# as14120_x31_fpga_cypress.net
KiCad netlist of a schematic drawn in Altium Designer
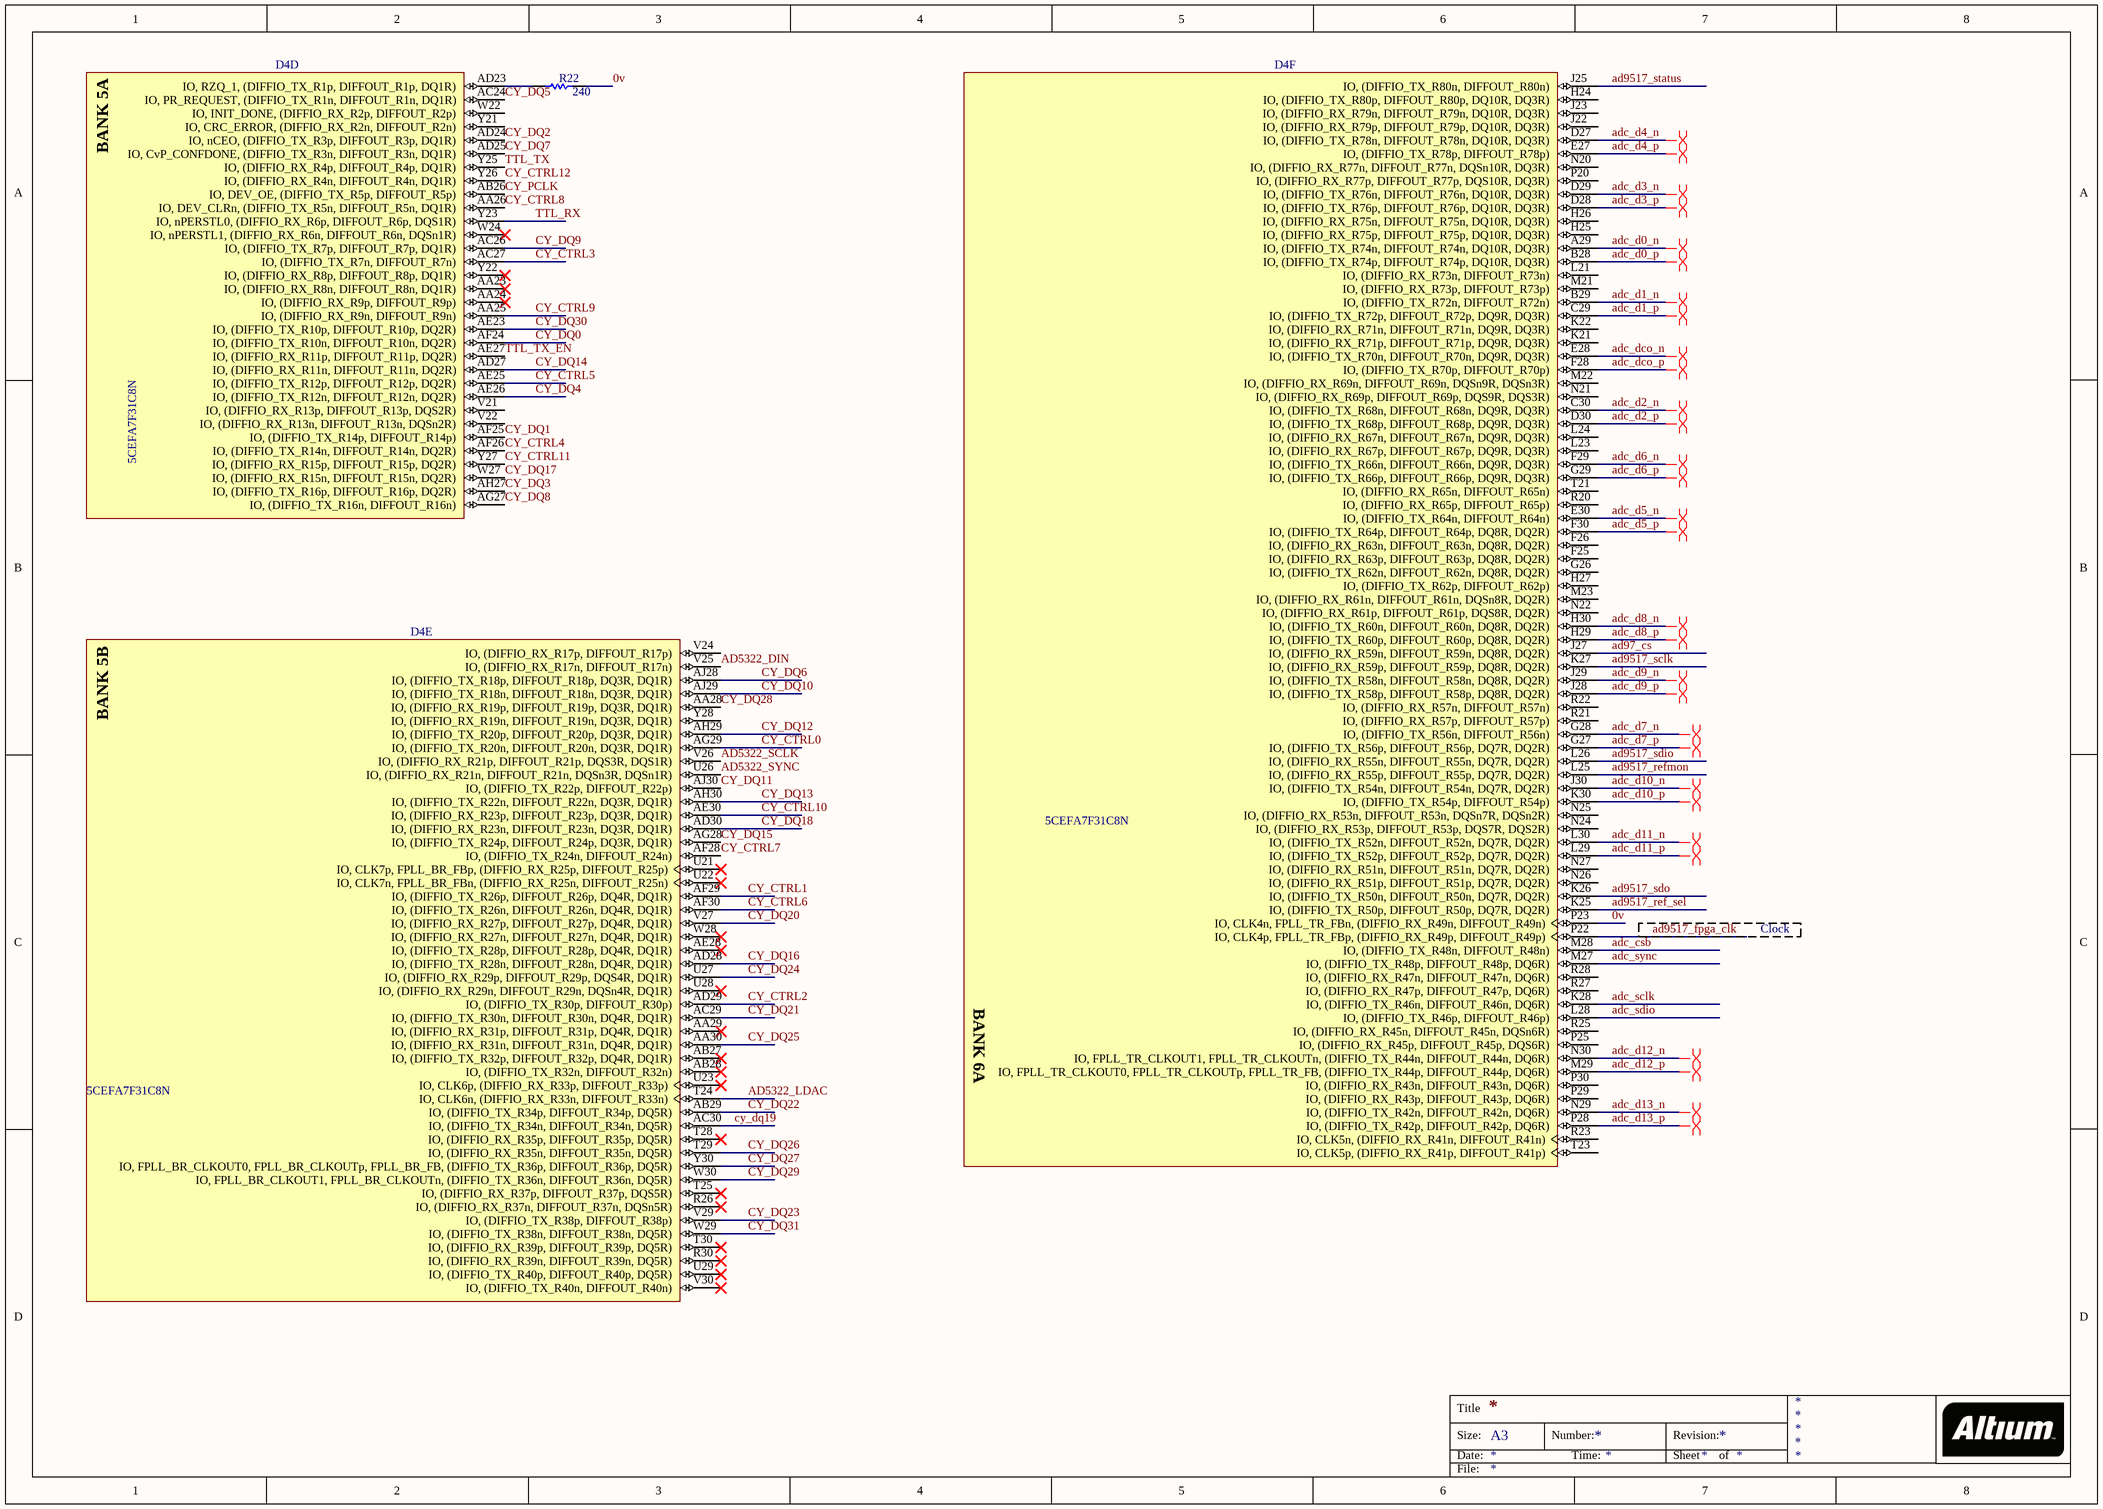
[diagram p0: as14120_x31_fpga_cypress.SchDoc]

(export (version "E")
  (design (tool "Eeschema 10.0.6"))
  (components
    (comp (ref "D4")
      (value "5CEFA7F31C8N")
      (footprint "ALTR-896-FBGA-2000A")
      (fields (field (name "MANUFACTURER") "Altera"))
      (libsource (lib "Altera Cyclone V E") (part "5CEFA7F31C8N"))
    )
    (comp (ref "R22")
      (value "240")
      (footprint "RESC0603(1608)_L")
      (description "1K 0.1W 5% 0603 (1608 Metric)  SMD")
      (fields (field (name "TOLERANCE") "5 %") (field (name "POWER") "0.1 W"))
      (libsource (lib "as14120") (part "RES_0603"))
    )
  )
  (nets
    (net (code "1") (name "/0v") (class "Default")
      (node (ref "D4") (pin "P23") (pinfunction "IO,_CLK4n,_FPLL_TR_FBn,_(DIFFIO_RX_R49n,_DIFFOUT_R49n)_P23") (pintype "bidirectional"))
      (node (ref "R22") (pin "2") (pinfunction "2_2") (pintype "passive"))
    )
    (net (code "2") (name "/AD5322_DIN") (class "Default")
      (node (ref "D4") (pin "V25") (pinfunction "IO,_(DIFFIO_RX_R17n,_DIFFOUT_R17n)_V25") (pintype "bidirectional"))
    )
    (net (code "3") (name "/AD5322_LDAC") (class "Default")
      (node (ref "D4") (pin "T24") (pinfunction "IO,_CLK6n,_(DIFFIO_RX_R33n,_DIFFOUT_R33n)_T24") (pintype "bidirectional"))
    )
    (net (code "4") (name "/AD5322_SCLK") (class "Default")
      (node (ref "D4") (pin "V26") (pinfunction "IO,_(DIFFIO_RX_R21p,_DIFFOUT_R21p,_DQS3R,_DQS1R)_V26") (pintype "bidirectional"))
    )
    (net (code "5") (name "/AD5322_SYNC") (class "Default")
      (node (ref "D4") (pin "U26") (pinfunction "IO,_(DIFFIO_RX_R21n,_DIFFOUT_R21n,_DQSn3R,_DQSn1R)_U26") (pintype "bidirectional"))
    )
    (net (code "6") (name "/CY_CTRL0") (class "Default")
      (node (ref "D4") (pin "AG29") (pinfunction "IO,_(DIFFIO_TX_R20n,_DIFFOUT_R20n,_DQ3R,_DQ1R)_AG29") (pintype "bidirectional"))
    )
    (net (code "7") (name "/CY_CTRL1") (class "Default")
      (node (ref "D4") (pin "AF29") (pinfunction "IO,_(DIFFIO_TX_R26p,_DIFFOUT_R26p,_DQ4R,_DQ1R)_AF29") (pintype "bidirectional"))
    )
    (net (code "8") (name "/CY_CTRL2") (class "Default")
      (node (ref "D4") (pin "AD29") (pinfunction "IO,_(DIFFIO_TX_R30p,_DIFFOUT_R30p)_AD29") (pintype "bidirectional"))
    )
    (net (code "9") (name "/CY_CTRL3") (class "Default")
      (node (ref "D4") (pin "AC27") (pinfunction "IO,_(DIFFIO_TX_R7n,_DIFFOUT_R7n)_AC27") (pintype "bidirectional"))
    )
    (net (code "10") (name "/CY_CTRL4") (class "Default")
      (node (ref "D4") (pin "AF26") (pinfunction "IO,_(DIFFIO_TX_R14n,_DIFFOUT_R14n,_DQ2R)_AF26") (pintype "bidirectional"))
    )
    (net (code "11") (name "/CY_CTRL5") (class "Default")
      (node (ref "D4") (pin "AE25") (pinfunction "IO,_(DIFFIO_TX_R12p,_DIFFOUT_R12p,_DQ2R)_AE25") (pintype "bidirectional"))
    )
    (net (code "12") (name "/CY_CTRL6") (class "Default")
      (node (ref "D4") (pin "AF30") (pinfunction "IO,_(DIFFIO_TX_R26n,_DIFFOUT_R26n,_DQ4R,_DQ1R)_AF30") (pintype "bidirectional"))
    )
    (net (code "13") (name "/CY_CTRL7") (class "Default")
      (node (ref "D4") (pin "AF28") (pinfunction "IO,_(DIFFIO_TX_R24n,_DIFFOUT_R24n)_AF28") (pintype "bidirectional"))
    )
    (net (code "14") (name "/CY_CTRL8") (class "Default")
      (node (ref "D4") (pin "AA26") (pinfunction "IO,_DEV_CLRn,_(DIFFIO_TX_R5n,_DIFFOUT_R5n,_DQ1R)_AA26") (pintype "bidirectional"))
    )
    (net (code "15") (name "/CY_CTRL9") (class "Default")
      (node (ref "D4") (pin "AA25") (pinfunction "IO,_(DIFFIO_RX_R9n,_DIFFOUT_R9n)_AA25") (pintype "bidirectional"))
    )
    (net (code "16") (name "/CY_CTRL10") (class "Default")
      (node (ref "D4") (pin "AE30") (pinfunction "IO,_(DIFFIO_RX_R23p,_DIFFOUT_R23p,_DQ3R,_DQ1R)_AE30") (pintype "bidirectional"))
    )
    (net (code "17") (name "/CY_CTRL11") (class "Default")
      (node (ref "D4") (pin "Y27") (pinfunction "IO,_(DIFFIO_RX_R15p,_DIFFOUT_R15p,_DQ2R)_Y27") (pintype "bidirectional"))
    )
    (net (code "18") (name "/CY_CTRL12") (class "Default")
      (node (ref "D4") (pin "Y26") (pinfunction "IO,_(DIFFIO_RX_R4n,_DIFFOUT_R4n,_DQ1R)_Y26") (pintype "bidirectional"))
    )
    (net (code "19") (name "/CY_DQ0") (class "Default")
      (node (ref "D4") (pin "AF24") (pinfunction "IO,_(DIFFIO_TX_R10n,_DIFFOUT_R10n,_DQ2R)_AF24") (pintype "bidirectional"))
    )
    (net (code "20") (name "/CY_DQ1") (class "Default")
      (node (ref "D4") (pin "AF25") (pinfunction "IO,_(DIFFIO_TX_R14p,_DIFFOUT_R14p)_AF25") (pintype "bidirectional"))
    )
    (net (code "21") (name "/CY_DQ2") (class "Default")
      (node (ref "D4") (pin "AD24") (pinfunction "IO,_nCEO,_(DIFFIO_TX_R3p,_DIFFOUT_R3p,_DQ1R)_AD24") (pintype "bidirectional"))
    )
    (net (code "22") (name "/CY_DQ3") (class "Default")
      (node (ref "D4") (pin "AH27") (pinfunction "IO,_(DIFFIO_TX_R16p,_DIFFOUT_R16p,_DQ2R)_AH27") (pintype "bidirectional"))
    )
    (net (code "23") (name "/CY_DQ4") (class "Default")
      (node (ref "D4") (pin "AE26") (pinfunction "IO,_(DIFFIO_TX_R12n,_DIFFOUT_R12n,_DQ2R)_AE26") (pintype "bidirectional"))
    )
    (net (code "24") (name "/CY_DQ5") (class "Default")
      (node (ref "D4") (pin "AC24") (pinfunction "IO,_PR_REQUEST,_(DIFFIO_TX_R1n,_DIFFOUT_R1n,_DQ1R)_AC24") (pintype "bidirectional"))
    )
    (net (code "25") (name "/CY_DQ6") (class "Default")
      (node (ref "D4") (pin "AJ28") (pinfunction "IO,_(DIFFIO_TX_R18p,_DIFFOUT_R18p,_DQ3R,_DQ1R)_AJ28") (pintype "bidirectional"))
    )
    (net (code "26") (name "/CY_DQ7") (class "Default")
      (node (ref "D4") (pin "AD25") (pinfunction "IO,_CvP_CONFDONE,_(DIFFIO_TX_R3n,_DIFFOUT_R3n,_DQ1R)_AD25") (pintype "bidirectional"))
    )
    (net (code "27") (name "/CY_DQ8") (class "Default")
      (node (ref "D4") (pin "AG27") (pinfunction "IO,_(DIFFIO_TX_R16n,_DIFFOUT_R16n)_AG27") (pintype "bidirectional"))
    )
    (net (code "28") (name "/CY_DQ9") (class "Default")
      (node (ref "D4") (pin "AC26") (pinfunction "IO,_(DIFFIO_TX_R7p,_DIFFOUT_R7p,_DQ1R)_AC26") (pintype "bidirectional"))
    )
    (net (code "29") (name "/CY_DQ10") (class "Default")
      (node (ref "D4") (pin "AJ29") (pinfunction "IO,_(DIFFIO_TX_R18n,_DIFFOUT_R18n,_DQ3R,_DQ1R)_AJ29") (pintype "bidirectional"))
    )
    (net (code "30") (name "/CY_DQ11") (class "Default")
      (node (ref "D4") (pin "AJ30") (pinfunction "IO,_(DIFFIO_TX_R22p,_DIFFOUT_R22p)_AJ30") (pintype "bidirectional"))
    )
    (net (code "31") (name "/CY_DQ12") (class "Default")
      (node (ref "D4") (pin "AH29") (pinfunction "IO,_(DIFFIO_TX_R20p,_DIFFOUT_R20p,_DQ3R,_DQ1R)_AH29") (pintype "bidirectional"))
    )
    (net (code "32") (name "/CY_DQ13") (class "Default")
      (node (ref "D4") (pin "AH30") (pinfunction "IO,_(DIFFIO_TX_R22n,_DIFFOUT_R22n,_DQ3R,_DQ1R)_AH30") (pintype "bidirectional"))
    )
    (net (code "33") (name "/CY_DQ14") (class "Default")
      (node (ref "D4") (pin "AD27") (pinfunction "IO,_(DIFFIO_RX_R11n,_DIFFOUT_R11n,_DQ2R)_AD27") (pintype "bidirectional"))
    )
    (net (code "34") (name "/CY_DQ15") (class "Default")
      (node (ref "D4") (pin "AG28") (pinfunction "IO,_(DIFFIO_TX_R24p,_DIFFOUT_R24p,_DQ3R,_DQ1R)_AG28") (pintype "bidirectional"))
    )
    (net (code "35") (name "/CY_DQ16") (class "Default")
      (node (ref "D4") (pin "AD28") (pinfunction "IO,_(DIFFIO_TX_R28n,_DIFFOUT_R28n,_DQ4R,_DQ1R)_AD28") (pintype "bidirectional"))
    )
    (net (code "36") (name "/CY_DQ17") (class "Default")
      (node (ref "D4") (pin "W27") (pinfunction "IO,_(DIFFIO_RX_R15n,_DIFFOUT_R15n,_DQ2R)_W27") (pintype "bidirectional"))
    )
    (net (code "37") (name "/CY_DQ18") (class "Default")
      (node (ref "D4") (pin "AD30") (pinfunction "IO,_(DIFFIO_RX_R23n,_DIFFOUT_R23n,_DQ3R,_DQ1R)_AD30") (pintype "bidirectional"))
    )
    (net (code "38") (name "/CY_DQ20") (class "Default")
      (node (ref "D4") (pin "V27") (pinfunction "IO,_(DIFFIO_RX_R27p,_DIFFOUT_R27p,_DQ4R,_DQ1R)_V27") (pintype "bidirectional"))
    )
    (net (code "39") (name "/CY_DQ21") (class "Default")
      (node (ref "D4") (pin "AC29") (pinfunction "IO,_(DIFFIO_TX_R30n,_DIFFOUT_R30n,_DQ4R,_DQ1R)_AC29") (pintype "bidirectional"))
    )
    (net (code "40") (name "/CY_DQ22") (class "Default")
      (node (ref "D4") (pin "AB29") (pinfunction "IO,_(DIFFIO_TX_R34p,_DIFFOUT_R34p,_DQ5R)_AB29") (pintype "bidirectional"))
    )
    (net (code "41") (name "/CY_DQ23") (class "Default")
      (node (ref "D4") (pin "V29") (pinfunction "IO,_(DIFFIO_TX_R38p,_DIFFOUT_R38p)_V29") (pintype "bidirectional"))
    )
    (net (code "42") (name "/CY_DQ24") (class "Default")
      (node (ref "D4") (pin "U27") (pinfunction "IO,_(DIFFIO_RX_R29p,_DIFFOUT_R29p,_DQS4R,_DQ1R)_U27") (pintype "bidirectional"))
    )
    (net (code "43") (name "/CY_DQ25") (class "Default")
      (node (ref "D4") (pin "AA30") (pinfunction "IO,_(DIFFIO_RX_R31n,_DIFFOUT_R31n,_DQ4R,_DQ1R)_AA30") (pintype "bidirectional"))
    )
    (net (code "44") (name "/CY_DQ26") (class "Default")
      (node (ref "D4") (pin "T29") (pinfunction "IO,_(DIFFIO_RX_R35n,_DIFFOUT_R35n,_DQ5R)_T29") (pintype "bidirectional"))
    )
    (net (code "45") (name "/CY_DQ27") (class "Default")
      (node (ref "D4") (pin "Y30") (pinfunction "IO,_FPLL_BR_CLKOUT0,_FPLL_BR_CLKOUTp,_FPLL_BR_FB,_(DIFFIO_TX_R36p,_DIFFOUT_R36p,_DQ5R)_Y30") (pintype "bidirectional"))
    )
    (net (code "46") (name "/CY_DQ28") (class "Default")
      (node (ref "D4") (pin "AA28") (pinfunction "IO,_(DIFFIO_RX_R19p,_DIFFOUT_R19p,_DQ3R,_DQ1R)_AA28") (pintype "bidirectional"))
    )
    (net (code "47") (name "/CY_DQ29") (class "Default")
      (node (ref "D4") (pin "W30") (pinfunction "IO,_FPLL_BR_CLKOUT1,_FPLL_BR_CLKOUTn,_(DIFFIO_TX_R36n,_DIFFOUT_R36n,_DQ5R)_W30") (pintype "bidirectional"))
    )
    (net (code "48") (name "/CY_DQ30") (class "Default")
      (node (ref "D4") (pin "AE23") (pinfunction "IO,_(DIFFIO_TX_R10p,_DIFFOUT_R10p,_DQ2R)_AE23") (pintype "bidirectional"))
    )
    (net (code "49") (name "/CY_DQ31") (class "Default")
      (node (ref "D4") (pin "W29") (pinfunction "IO,_(DIFFIO_TX_R38n,_DIFFOUT_R38n,_DQ5R)_W29") (pintype "bidirectional"))
    )
    (net (code "50") (name "/CY_PCLK") (class "Default")
      (node (ref "D4") (pin "AB26") (pinfunction "IO,_DEV_OE,_(DIFFIO_TX_R5p,_DIFFOUT_R5p)_AB26") (pintype "bidirectional"))
    )
    (net (code "51") (name "/TTL_RX") (class "Default")
      (node (ref "D4") (pin "Y23") (pinfunction "IO,_nPERSTL0,_(DIFFIO_RX_R6p,_DIFFOUT_R6p,_DQS1R)_Y23") (pintype "bidirectional"))
    )
    (net (code "52") (name "/TTL_TX") (class "Default")
      (node (ref "D4") (pin "Y25") (pinfunction "IO,_(DIFFIO_RX_R4p,_DIFFOUT_R4p,_DQ1R)_Y25") (pintype "bidirectional"))
    )
    (net (code "53") (name "/TTL_TX_EN") (class "Default")
      (node (ref "D4") (pin "AE27") (pinfunction "IO,_(DIFFIO_RX_R11p,_DIFFOUT_R11p,_DQ2R)_AE27") (pintype "bidirectional"))
    )
    (net (code "54") (name "/ad97_cs") (class "Default")
      (node (ref "D4") (pin "J27") (pinfunction "IO,_(DIFFIO_RX_R59n,_DIFFOUT_R59n,_DQ8R,_DQ2R)_J27") (pintype "bidirectional"))
    )
    (net (code "55") (name "/ad9517_fpga_clk") (class "Default")
      (node (ref "D4") (pin "P22") (pinfunction "IO,_CLK4p,_FPLL_TR_FBp,_(DIFFIO_RX_R49p,_DIFFOUT_R49p)_P22") (pintype "bidirectional"))
    )
    (net (code "56") (name "/ad9517_ref_sel") (class "Default")
      (node (ref "D4") (pin "K25") (pinfunction "IO,_(DIFFIO_TX_R50p,_DIFFOUT_R50p,_DQ7R,_DQ2R)_K25") (pintype "bidirectional"))
    )
    (net (code "57") (name "/ad9517_refmon") (class "Default")
      (node (ref "D4") (pin "L25") (pinfunction "IO,_(DIFFIO_RX_R55p,_DIFFOUT_R55p,_DQ7R,_DQ2R)_L25") (pintype "bidirectional"))
    )
    (net (code "58") (name "/ad9517_sclk") (class "Default")
      (node (ref "D4") (pin "K27") (pinfunction "IO,_(DIFFIO_RX_R59p,_DIFFOUT_R59p,_DQ8R,_DQ2R)_K27") (pintype "bidirectional"))
    )
    (net (code "59") (name "/ad9517_sdio") (class "Default")
      (node (ref "D4") (pin "L26") (pinfunction "IO,_(DIFFIO_RX_R55n,_DIFFOUT_R55n,_DQ7R,_DQ2R)_L26") (pintype "bidirectional"))
    )
    (net (code "60") (name "/ad9517_sdo") (class "Default")
      (node (ref "D4") (pin "K26") (pinfunction "IO,_(DIFFIO_TX_R50n,_DIFFOUT_R50n,_DQ7R,_DQ2R)_K26") (pintype "bidirectional"))
    )
    (net (code "61") (name "/ad9517_status") (class "Default")
      (node (ref "D4") (pin "J25") (pinfunction "IO,_(DIFFIO_TX_R80n,_DIFFOUT_R80n)_J25") (pintype "bidirectional"))
    )
    (net (code "62") (name "/adc_csb") (class "Default")
      (node (ref "D4") (pin "M28") (pinfunction "IO,_(DIFFIO_TX_R48n,_DIFFOUT_R48n)_M28") (pintype "bidirectional"))
    )
    (net (code "63") (name "/adc_d0_n") (class "Default")
      (node (ref "D4") (pin "A29") (pinfunction "IO,_(DIFFIO_TX_R74n,_DIFFOUT_R74n,_DQ10R,_DQ3R)_A29") (pintype "bidirectional"))
    )
    (net (code "64") (name "/adc_d0_p") (class "Default")
      (node (ref "D4") (pin "B28") (pinfunction "IO,_(DIFFIO_TX_R74p,_DIFFOUT_R74p,_DQ10R,_DQ3R)_B28") (pintype "bidirectional"))
    )
    (net (code "65") (name "/adc_d1_n") (class "Default")
      (node (ref "D4") (pin "B29") (pinfunction "IO,_(DIFFIO_TX_R72n,_DIFFOUT_R72n)_B29") (pintype "bidirectional"))
    )
    (net (code "66") (name "/adc_d1_p") (class "Default")
      (node (ref "D4") (pin "C29") (pinfunction "IO,_(DIFFIO_TX_R72p,_DIFFOUT_R72p,_DQ9R,_DQ3R)_C29") (pintype "bidirectional"))
    )
    (net (code "67") (name "/adc_d2_n") (class "Default")
      (node (ref "D4") (pin "C30") (pinfunction "IO,_(DIFFIO_TX_R68n,_DIFFOUT_R68n,_DQ9R,_DQ3R)_C30") (pintype "bidirectional"))
    )
    (net (code "68") (name "/adc_d2_p") (class "Default")
      (node (ref "D4") (pin "D30") (pinfunction "IO,_(DIFFIO_TX_R68p,_DIFFOUT_R68p,_DQ9R,_DQ3R)_D30") (pintype "bidirectional"))
    )
    (net (code "69") (name "/adc_d3_n") (class "Default")
      (node (ref "D4") (pin "D29") (pinfunction "IO,_(DIFFIO_TX_R76n,_DIFFOUT_R76n,_DQ10R,_DQ3R)_D29") (pintype "bidirectional"))
    )
    (net (code "70") (name "/adc_d3_p") (class "Default")
      (node (ref "D4") (pin "D28") (pinfunction "IO,_(DIFFIO_TX_R76p,_DIFFOUT_R76p,_DQ10R,_DQ3R)_D28") (pintype "bidirectional"))
    )
    (net (code "71") (name "/adc_d4_n") (class "Default")
      (node (ref "D4") (pin "D27") (pinfunction "IO,_(DIFFIO_TX_R78n,_DIFFOUT_R78n,_DQ10R,_DQ3R)_D27") (pintype "bidirectional"))
    )
    (net (code "72") (name "/adc_d4_p") (class "Default")
      (node (ref "D4") (pin "E27") (pinfunction "IO,_(DIFFIO_TX_R78p,_DIFFOUT_R78p)_E27") (pintype "bidirectional"))
    )
    (net (code "73") (name "/adc_d5_n") (class "Default")
      (node (ref "D4") (pin "E30") (pinfunction "IO,_(DIFFIO_TX_R64n,_DIFFOUT_R64n)_E30") (pintype "bidirectional"))
    )
    (net (code "74") (name "/adc_d5_p") (class "Default")
      (node (ref "D4") (pin "F30") (pinfunction "IO,_(DIFFIO_TX_R64p,_DIFFOUT_R64p,_DQ8R,_DQ2R)_F30") (pintype "bidirectional"))
    )
    (net (code "75") (name "/adc_d6_n") (class "Default")
      (node (ref "D4") (pin "F29") (pinfunction "IO,_(DIFFIO_TX_R66n,_DIFFOUT_R66n,_DQ9R,_DQ3R)_F29") (pintype "bidirectional"))
    )
    (net (code "76") (name "/adc_d6_p") (class "Default")
      (node (ref "D4") (pin "G29") (pinfunction "IO,_(DIFFIO_TX_R66p,_DIFFOUT_R66p,_DQ9R,_DQ3R)_G29") (pintype "bidirectional"))
    )
    (net (code "77") (name "/adc_d7_n") (class "Default")
      (node (ref "D4") (pin "G28") (pinfunction "IO,_(DIFFIO_TX_R56n,_DIFFOUT_R56n)_G28") (pintype "bidirectional"))
    )
    (net (code "78") (name "/adc_d7_p") (class "Default")
      (node (ref "D4") (pin "G27") (pinfunction "IO,_(DIFFIO_TX_R56p,_DIFFOUT_R56p,_DQ7R,_DQ2R)_G27") (pintype "bidirectional"))
    )
    (net (code "79") (name "/adc_d8_n") (class "Default")
      (node (ref "D4") (pin "H30") (pinfunction "IO,_(DIFFIO_TX_R60n,_DIFFOUT_R60n,_DQ8R,_DQ2R)_H30") (pintype "bidirectional"))
    )
    (net (code "80") (name "/adc_d8_p") (class "Default")
      (node (ref "D4") (pin "H29") (pinfunction "IO,_(DIFFIO_TX_R60p,_DIFFOUT_R60p,_DQ8R,_DQ2R)_H29") (pintype "bidirectional"))
    )
    (net (code "81") (name "/adc_d9_n") (class "Default")
      (node (ref "D4") (pin "J29") (pinfunction "IO,_(DIFFIO_TX_R58n,_DIFFOUT_R58n,_DQ8R,_DQ2R)_J29") (pintype "bidirectional"))
    )
    (net (code "82") (name "/adc_d9_p") (class "Default")
      (node (ref "D4") (pin "J28") (pinfunction "IO,_(DIFFIO_TX_R58p,_DIFFOUT_R58p,_DQ8R,_DQ2R)_J28") (pintype "bidirectional"))
    )
    (net (code "83") (name "/adc_d10_n") (class "Default")
      (node (ref "D4") (pin "J30") (pinfunction "IO,_(DIFFIO_TX_R54n,_DIFFOUT_R54n,_DQ7R,_DQ2R)_J30") (pintype "bidirectional"))
    )
    (net (code "84") (name "/adc_d10_p") (class "Default")
      (node (ref "D4") (pin "K30") (pinfunction "IO,_(DIFFIO_TX_R54p,_DIFFOUT_R54p)_K30") (pintype "bidirectional"))
    )
    (net (code "85") (name "/adc_d11_n") (class "Default")
      (node (ref "D4") (pin "L30") (pinfunction "IO,_(DIFFIO_TX_R52n,_DIFFOUT_R52n,_DQ7R,_DQ2R)_L30") (pintype "bidirectional"))
    )
    (net (code "86") (name "/adc_d11_p") (class "Default")
      (node (ref "D4") (pin "L29") (pinfunction "IO,_(DIFFIO_TX_R52p,_DIFFOUT_R52p,_DQ7R,_DQ2R)_L29") (pintype "bidirectional"))
    )
    (net (code "87") (name "/adc_d12_n") (class "Default")
      (node (ref "D4") (pin "N30") (pinfunction "IO,_FPLL_TR_CLKOUT1,_FPLL_TR_CLKOUTn,_(DIFFIO_TX_R44n,_DIFFOUT_R44n,_DQ6R)_N30") (pintype "bidirectional"))
    )
    (net (code "88") (name "/adc_d12_p") (class "Default")
      (node (ref "D4") (pin "M29") (pinfunction "IO,_FPLL_TR_CLKOUT0,_FPLL_TR_CLKOUTp,_FPLL_TR_FB,_(DIFFIO_TX_R44p,_DIFFOUT_R44p,_DQ6R)_M29") (pintype "bidirectional"))
    )
    (net (code "89") (name "/adc_d13_n") (class "Default")
      (node (ref "D4") (pin "N29") (pinfunction "IO,_(DIFFIO_TX_R42n,_DIFFOUT_R42n,_DQ6R)_N29") (pintype "bidirectional"))
    )
    (net (code "90") (name "/adc_d13_p") (class "Default")
      (node (ref "D4") (pin "P28") (pinfunction "IO,_(DIFFIO_TX_R42p,_DIFFOUT_R42p,_DQ6R)_P28") (pintype "bidirectional"))
    )
    (net (code "91") (name "/adc_dco_n") (class "Default")
      (node (ref "D4") (pin "E28") (pinfunction "IO,_(DIFFIO_TX_R70n,_DIFFOUT_R70n,_DQ9R,_DQ3R)_E28") (pintype "bidirectional"))
    )
    (net (code "92") (name "/adc_dco_p") (class "Default")
      (node (ref "D4") (pin "F28") (pinfunction "IO,_(DIFFIO_TX_R70p,_DIFFOUT_R70p)_F28") (pintype "bidirectional"))
    )
    (net (code "93") (name "/adc_sclk") (class "Default")
      (node (ref "D4") (pin "K28") (pinfunction "IO,_(DIFFIO_TX_R46n,_DIFFOUT_R46n,_DQ6R)_K28") (pintype "bidirectional"))
    )
    (net (code "94") (name "/adc_sdio") (class "Default")
      (node (ref "D4") (pin "L28") (pinfunction "IO,_(DIFFIO_TX_R46p,_DIFFOUT_R46p)_L28") (pintype "bidirectional"))
    )
    (net (code "95") (name "/adc_sync") (class "Default")
      (node (ref "D4") (pin "M27") (pinfunction "IO,_(DIFFIO_TX_R48p,_DIFFOUT_R48p,_DQ6R)_M27") (pintype "bidirectional"))
    )
    (net (code "96") (name "/cy_dq19") (class "Default")
      (node (ref "D4") (pin "AC30") (pinfunction "IO,_(DIFFIO_TX_R34n,_DIFFOUT_R34n,_DQ5R)_AC30") (pintype "bidirectional"))
    )
    (net (code "97") (name "Net-(D4D-IO,_RZQ_1,_(DIFFIO_TX_R1p,_DIFFOUT_R1p,_DQ1R))") (class "Default")
      (node (ref "D4") (pin "AD23") (pinfunction "IO,_RZQ_1,_(DIFFIO_TX_R1p,_DIFFOUT_R1p,_DQ1R)_AD23") (pintype "bidirectional"))
      (node (ref "R22") (pin "1") (pinfunction "1_1") (pintype "passive"))
    )
    (net (code "98") (name "unconnected-(D4D-IO,_(DIFFIO_RX_R8n,_DIFFOUT_R8n,_DQ1R)-PadAA23)") (class "Default")
      (node (ref "D4") (pin "AA23") (pinfunction "IO,_(DIFFIO_RX_R8n,_DIFFOUT_R8n,_DQ1R)_AA23") (pintype "bidirectional+no_connect"))
    )
    (net (code "99") (name "unconnected-(D4D-IO,_(DIFFIO_RX_R8p,_DIFFOUT_R8p,_DQ1R)-PadY22)") (class "Default")
      (node (ref "D4") (pin "Y22") (pinfunction "IO,_(DIFFIO_RX_R8p,_DIFFOUT_R8p,_DQ1R)_Y22") (pintype "bidirectional+no_connect"))
    )
    (net (code "100") (name "unconnected-(D4D-IO,_(DIFFIO_RX_R9p,_DIFFOUT_R9p)-PadAA24)") (class "Default")
      (node (ref "D4") (pin "AA24") (pinfunction "IO,_(DIFFIO_RX_R9p,_DIFFOUT_R9p)_AA24") (pintype "bidirectional+no_connect"))
    )
    (net (code "101") (name "unconnected-(D4D-IO,_(DIFFIO_RX_R13n,_DIFFOUT_R13n,_DQSn2R)-PadV22)") (class "Default")
      (node (ref "D4") (pin "V22") (pinfunction "IO,_(DIFFIO_RX_R13n,_DIFFOUT_R13n,_DQSn2R)_V22") (pintype "bidirectional"))
    )
    (net (code "102") (name "unconnected-(D4D-IO,_(DIFFIO_RX_R13p,_DIFFOUT_R13p,_DQS2R)-PadV21)") (class "Default")
      (node (ref "D4") (pin "V21") (pinfunction "IO,_(DIFFIO_RX_R13p,_DIFFOUT_R13p,_DQS2R)_V21") (pintype "bidirectional"))
    )
    (net (code "103") (name "unconnected-(D4D-IO,_CRC_ERROR,_(DIFFIO_RX_R2n,_DIFFOUT_R2n)-PadY21)") (class "Default")
      (node (ref "D4") (pin "Y21") (pinfunction "IO,_CRC_ERROR,_(DIFFIO_RX_R2n,_DIFFOUT_R2n)_Y21") (pintype "bidirectional"))
    )
    (net (code "104") (name "unconnected-(D4D-IO,_INIT_DONE,_(DIFFIO_RX_R2p,_DIFFOUT_R2p)-PadW22)") (class "Default")
      (node (ref "D4") (pin "W22") (pinfunction "IO,_INIT_DONE,_(DIFFIO_RX_R2p,_DIFFOUT_R2p)_W22") (pintype "bidirectional"))
    )
    (net (code "105") (name "unconnected-(D4D-IO,_nPERSTL1,_(DIFFIO_RX_R6n,_DIFFOUT_R6n,_DQSn1R)-PadW24)") (class "Default")
      (node (ref "D4") (pin "W24") (pinfunction "IO,_nPERSTL1,_(DIFFIO_RX_R6n,_DIFFOUT_R6n,_DQSn1R)_W24") (pintype "bidirectional+no_connect"))
    )
    (net (code "106") (name "unconnected-(D4E-IO,_(DIFFIO_RX_R17p,_DIFFOUT_R17p)-PadV24)") (class "Default")
      (node (ref "D4") (pin "V24") (pinfunction "IO,_(DIFFIO_RX_R17p,_DIFFOUT_R17p)_V24") (pintype "bidirectional"))
    )
    (net (code "107") (name "unconnected-(D4E-IO,_(DIFFIO_RX_R19n,_DIFFOUT_R19n,_DQ3R,_DQ1R)-PadY28)") (class "Default")
      (node (ref "D4") (pin "Y28") (pinfunction "IO,_(DIFFIO_RX_R19n,_DIFFOUT_R19n,_DQ3R,_DQ1R)_Y28") (pintype "bidirectional"))
    )
    (net (code "108") (name "unconnected-(D4E-IO,_(DIFFIO_RX_R27n,_DIFFOUT_R27n,_DQ4R,_DQ1R)-PadW28)") (class "Default")
      (node (ref "D4") (pin "W28") (pinfunction "IO,_(DIFFIO_RX_R27n,_DIFFOUT_R27n,_DQ4R,_DQ1R)_W28") (pintype "bidirectional+no_connect"))
    )
    (net (code "109") (name "unconnected-(D4E-IO,_(DIFFIO_RX_R29n,_DIFFOUT_R29n,_DQSn4R,_DQ1R)-PadU28)") (class "Default")
      (node (ref "D4") (pin "U28") (pinfunction "IO,_(DIFFIO_RX_R29n,_DIFFOUT_R29n,_DQSn4R,_DQ1R)_U28") (pintype "bidirectional+no_connect"))
    )
    (net (code "110") (name "unconnected-(D4E-IO,_(DIFFIO_RX_R31p,_DIFFOUT_R31p,_DQ4R,_DQ1R)-PadAA29)") (class "Default")
      (node (ref "D4") (pin "AA29") (pinfunction "IO,_(DIFFIO_RX_R31p,_DIFFOUT_R31p,_DQ4R,_DQ1R)_AA29") (pintype "bidirectional+no_connect"))
    )
    (net (code "111") (name "unconnected-(D4E-IO,_(DIFFIO_RX_R35p,_DIFFOUT_R35p,_DQ5R)-PadT28)") (class "Default")
      (node (ref "D4") (pin "T28") (pinfunction "IO,_(DIFFIO_RX_R35p,_DIFFOUT_R35p,_DQ5R)_T28") (pintype "bidirectional+no_connect"))
    )
    (net (code "112") (name "unconnected-(D4E-IO,_(DIFFIO_RX_R37n,_DIFFOUT_R37n,_DQSn5R)-PadR26)") (class "Default")
      (node (ref "D4") (pin "R26") (pinfunction "IO,_(DIFFIO_RX_R37n,_DIFFOUT_R37n,_DQSn5R)_R26") (pintype "bidirectional+no_connect"))
    )
    (net (code "113") (name "unconnected-(D4E-IO,_(DIFFIO_RX_R37p,_DIFFOUT_R37p,_DQS5R)-PadT25)") (class "Default")
      (node (ref "D4") (pin "T25") (pinfunction "IO,_(DIFFIO_RX_R37p,_DIFFOUT_R37p,_DQS5R)_T25") (pintype "bidirectional+no_connect"))
    )
    (net (code "114") (name "unconnected-(D4E-IO,_(DIFFIO_RX_R39n,_DIFFOUT_R39n,_DQ5R)-PadR30)") (class "Default")
      (node (ref "D4") (pin "R30") (pinfunction "IO,_(DIFFIO_RX_R39n,_DIFFOUT_R39n,_DQ5R)_R30") (pintype "bidirectional+no_connect"))
    )
    (net (code "115") (name "unconnected-(D4E-IO,_(DIFFIO_RX_R39p,_DIFFOUT_R39p,_DQ5R)-PadT30)") (class "Default")
      (node (ref "D4") (pin "T30") (pinfunction "IO,_(DIFFIO_RX_R39p,_DIFFOUT_R39p,_DQ5R)_T30") (pintype "bidirectional+no_connect"))
    )
    (net (code "116") (name "unconnected-(D4E-IO,_(DIFFIO_TX_R28p,_DIFFOUT_R28p,_DQ4R,_DQ1R)-PadAE28)") (class "Default")
      (node (ref "D4") (pin "AE28") (pinfunction "IO,_(DIFFIO_TX_R28p,_DIFFOUT_R28p,_DQ4R,_DQ1R)_AE28") (pintype "bidirectional+no_connect"))
    )
    (net (code "117") (name "unconnected-(D4E-IO,_(DIFFIO_TX_R32n,_DIFFOUT_R32n)-PadAB28)") (class "Default")
      (node (ref "D4") (pin "AB28") (pinfunction "IO,_(DIFFIO_TX_R32n,_DIFFOUT_R32n)_AB28") (pintype "bidirectional+no_connect"))
    )
    (net (code "118") (name "unconnected-(D4E-IO,_(DIFFIO_TX_R32p,_DIFFOUT_R32p,_DQ4R,_DQ1R)-PadAB27)") (class "Default")
      (node (ref "D4") (pin "AB27") (pinfunction "IO,_(DIFFIO_TX_R32p,_DIFFOUT_R32p,_DQ4R,_DQ1R)_AB27") (pintype "bidirectional+no_connect"))
    )
    (net (code "119") (name "unconnected-(D4E-IO,_(DIFFIO_TX_R40n,_DIFFOUT_R40n)-PadV30)") (class "Default")
      (node (ref "D4") (pin "V30") (pinfunction "IO,_(DIFFIO_TX_R40n,_DIFFOUT_R40n)_V30") (pintype "bidirectional+no_connect"))
    )
    (net (code "120") (name "unconnected-(D4E-IO,_(DIFFIO_TX_R40p,_DIFFOUT_R40p,_DQ5R)-PadU29)") (class "Default")
      (node (ref "D4") (pin "U29") (pinfunction "IO,_(DIFFIO_TX_R40p,_DIFFOUT_R40p,_DQ5R)_U29") (pintype "bidirectional+no_connect"))
    )
    (net (code "121") (name "unconnected-(D4E-IO,_CLK6p,_(DIFFIO_RX_R33p,_DIFFOUT_R33p)-PadU23)") (class "Default")
      (node (ref "D4") (pin "U23") (pinfunction "IO,_CLK6p,_(DIFFIO_RX_R33p,_DIFFOUT_R33p)_U23") (pintype "bidirectional+no_connect"))
    )
    (net (code "122") (name "unconnected-(D4E-IO,_CLK7n,_FPLL_BR_FBn,_(DIFFIO_RX_R25n,_DIFFOUT_R25n)-PadU22)") (class "Default")
      (node (ref "D4") (pin "U22") (pinfunction "IO,_CLK7n,_FPLL_BR_FBn,_(DIFFIO_RX_R25n,_DIFFOUT_R25n)_U22") (pintype "bidirectional+no_connect"))
    )
    (net (code "123") (name "unconnected-(D4E-IO,_CLK7p,_FPLL_BR_FBp,_(DIFFIO_RX_R25p,_DIFFOUT_R25p)-PadU21)") (class "Default")
      (node (ref "D4") (pin "U21") (pinfunction "IO,_CLK7p,_FPLL_BR_FBp,_(DIFFIO_RX_R25p,_DIFFOUT_R25p)_U21") (pintype "bidirectional+no_connect"))
    )
    (net (code "124") (name "unconnected-(D4F-IO,_(DIFFIO_RX_R43n,_DIFFOUT_R43n,_DQ6R)-PadP30)") (class "Default")
      (node (ref "D4") (pin "P30") (pinfunction "IO,_(DIFFIO_RX_R43n,_DIFFOUT_R43n,_DQ6R)_P30") (pintype "bidirectional"))
    )
    (net (code "125") (name "unconnected-(D4F-IO,_(DIFFIO_RX_R43p,_DIFFOUT_R43p,_DQ6R)-PadP29)") (class "Default")
      (node (ref "D4") (pin "P29") (pinfunction "IO,_(DIFFIO_RX_R43p,_DIFFOUT_R43p,_DQ6R)_P29") (pintype "bidirectional"))
    )
    (net (code "126") (name "unconnected-(D4F-IO,_(DIFFIO_RX_R45n,_DIFFOUT_R45n,_DQSn6R)-PadR25)") (class "Default")
      (node (ref "D4") (pin "R25") (pinfunction "IO,_(DIFFIO_RX_R45n,_DIFFOUT_R45n,_DQSn6R)_R25") (pintype "bidirectional"))
    )
    (net (code "127") (name "unconnected-(D4F-IO,_(DIFFIO_RX_R45p,_DIFFOUT_R45p,_DQS6R)-PadP25)") (class "Default")
      (node (ref "D4") (pin "P25") (pinfunction "IO,_(DIFFIO_RX_R45p,_DIFFOUT_R45p,_DQS6R)_P25") (pintype "bidirectional"))
    )
    (net (code "128") (name "unconnected-(D4F-IO,_(DIFFIO_RX_R47n,_DIFFOUT_R47n,_DQ6R)-PadR28)") (class "Default")
      (node (ref "D4") (pin "R28") (pinfunction "IO,_(DIFFIO_RX_R47n,_DIFFOUT_R47n,_DQ6R)_R28") (pintype "bidirectional"))
    )
    (net (code "129") (name "unconnected-(D4F-IO,_(DIFFIO_RX_R47p,_DIFFOUT_R47p,_DQ6R)-PadR27)") (class "Default")
      (node (ref "D4") (pin "R27") (pinfunction "IO,_(DIFFIO_RX_R47p,_DIFFOUT_R47p,_DQ6R)_R27") (pintype "bidirectional"))
    )
    (net (code "130") (name "unconnected-(D4F-IO,_(DIFFIO_RX_R51n,_DIFFOUT_R51n,_DQ7R,_DQ2R)-PadN27)") (class "Default")
      (node (ref "D4") (pin "N27") (pinfunction "IO,_(DIFFIO_RX_R51n,_DIFFOUT_R51n,_DQ7R,_DQ2R)_N27") (pintype "bidirectional"))
    )
    (net (code "131") (name "unconnected-(D4F-IO,_(DIFFIO_RX_R51p,_DIFFOUT_R51p,_DQ7R,_DQ2R)-PadN26)") (class "Default")
      (node (ref "D4") (pin "N26") (pinfunction "IO,_(DIFFIO_RX_R51p,_DIFFOUT_R51p,_DQ7R,_DQ2R)_N26") (pintype "bidirectional"))
    )
    (net (code "132") (name "unconnected-(D4F-IO,_(DIFFIO_RX_R53n,_DIFFOUT_R53n,_DQSn7R,_DQSn2R)-PadN25)") (class "Default")
      (node (ref "D4") (pin "N25") (pinfunction "IO,_(DIFFIO_RX_R53n,_DIFFOUT_R53n,_DQSn7R,_DQSn2R)_N25") (pintype "bidirectional"))
    )
    (net (code "133") (name "unconnected-(D4F-IO,_(DIFFIO_RX_R53p,_DIFFOUT_R53p,_DQS7R,_DQS2R)-PadN24)") (class "Default")
      (node (ref "D4") (pin "N24") (pinfunction "IO,_(DIFFIO_RX_R53p,_DIFFOUT_R53p,_DQS7R,_DQS2R)_N24") (pintype "bidirectional"))
    )
    (net (code "134") (name "unconnected-(D4F-IO,_(DIFFIO_RX_R57n,_DIFFOUT_R57n)-PadR22)") (class "Default")
      (node (ref "D4") (pin "R22") (pinfunction "IO,_(DIFFIO_RX_R57n,_DIFFOUT_R57n)_R22") (pintype "bidirectional"))
    )
    (net (code "135") (name "unconnected-(D4F-IO,_(DIFFIO_RX_R57p,_DIFFOUT_R57p)-PadR21)") (class "Default")
      (node (ref "D4") (pin "R21") (pinfunction "IO,_(DIFFIO_RX_R57p,_DIFFOUT_R57p)_R21") (pintype "bidirectional"))
    )
    (net (code "136") (name "unconnected-(D4F-IO,_(DIFFIO_RX_R61n,_DIFFOUT_R61n,_DQSn8R,_DQ2R)-PadM23)") (class "Default")
      (node (ref "D4") (pin "M23") (pinfunction "IO,_(DIFFIO_RX_R61n,_DIFFOUT_R61n,_DQSn8R,_DQ2R)_M23") (pintype "bidirectional"))
    )
    (net (code "137") (name "unconnected-(D4F-IO,_(DIFFIO_RX_R61p,_DIFFOUT_R61p,_DQS8R,_DQ2R)-PadN22)") (class "Default")
      (node (ref "D4") (pin "N22") (pinfunction "IO,_(DIFFIO_RX_R61p,_DIFFOUT_R61p,_DQS8R,_DQ2R)_N22") (pintype "bidirectional"))
    )
    (net (code "138") (name "unconnected-(D4F-IO,_(DIFFIO_RX_R63n,_DIFFOUT_R63n,_DQ8R,_DQ2R)-PadF26)") (class "Default")
      (node (ref "D4") (pin "F26") (pinfunction "IO,_(DIFFIO_RX_R63n,_DIFFOUT_R63n,_DQ8R,_DQ2R)_F26") (pintype "bidirectional"))
    )
    (net (code "139") (name "unconnected-(D4F-IO,_(DIFFIO_RX_R63p,_DIFFOUT_R63p,_DQ8R,_DQ2R)-PadF25)") (class "Default")
      (node (ref "D4") (pin "F25") (pinfunction "IO,_(DIFFIO_RX_R63p,_DIFFOUT_R63p,_DQ8R,_DQ2R)_F25") (pintype "bidirectional"))
    )
    (net (code "140") (name "unconnected-(D4F-IO,_(DIFFIO_RX_R65n,_DIFFOUT_R65n)-PadT21)") (class "Default")
      (node (ref "D4") (pin "T21") (pinfunction "IO,_(DIFFIO_RX_R65n,_DIFFOUT_R65n)_T21") (pintype "bidirectional"))
    )
    (net (code "141") (name "unconnected-(D4F-IO,_(DIFFIO_RX_R65p,_DIFFOUT_R65p)-PadR20)") (class "Default")
      (node (ref "D4") (pin "R20") (pinfunction "IO,_(DIFFIO_RX_R65p,_DIFFOUT_R65p)_R20") (pintype "bidirectional"))
    )
    (net (code "142") (name "unconnected-(D4F-IO,_(DIFFIO_RX_R67n,_DIFFOUT_R67n,_DQ9R,_DQ3R)-PadL24)") (class "Default")
      (node (ref "D4") (pin "L24") (pinfunction "IO,_(DIFFIO_RX_R67n,_DIFFOUT_R67n,_DQ9R,_DQ3R)_L24") (pintype "bidirectional"))
    )
    (net (code "143") (name "unconnected-(D4F-IO,_(DIFFIO_RX_R67p,_DIFFOUT_R67p,_DQ9R,_DQ3R)-PadL23)") (class "Default")
      (node (ref "D4") (pin "L23") (pinfunction "IO,_(DIFFIO_RX_R67p,_DIFFOUT_R67p,_DQ9R,_DQ3R)_L23") (pintype "bidirectional"))
    )
    (net (code "144") (name "unconnected-(D4F-IO,_(DIFFIO_RX_R69n,_DIFFOUT_R69n,_DQSn9R,_DQSn3R)-PadM22)") (class "Default")
      (node (ref "D4") (pin "M22") (pinfunction "IO,_(DIFFIO_RX_R69n,_DIFFOUT_R69n,_DQSn9R,_DQSn3R)_M22") (pintype "bidirectional"))
    )
    (net (code "145") (name "unconnected-(D4F-IO,_(DIFFIO_RX_R69p,_DIFFOUT_R69p,_DQS9R,_DQS3R)-PadN21)") (class "Default")
      (node (ref "D4") (pin "N21") (pinfunction "IO,_(DIFFIO_RX_R69p,_DIFFOUT_R69p,_DQS9R,_DQS3R)_N21") (pintype "bidirectional"))
    )
    (net (code "146") (name "unconnected-(D4F-IO,_(DIFFIO_RX_R71n,_DIFFOUT_R71n,_DQ9R,_DQ3R)-PadK22)") (class "Default")
      (node (ref "D4") (pin "K22") (pinfunction "IO,_(DIFFIO_RX_R71n,_DIFFOUT_R71n,_DQ9R,_DQ3R)_K22") (pintype "bidirectional"))
    )
    (net (code "147") (name "unconnected-(D4F-IO,_(DIFFIO_RX_R71p,_DIFFOUT_R71p,_DQ9R,_DQ3R)-PadK21)") (class "Default")
      (node (ref "D4") (pin "K21") (pinfunction "IO,_(DIFFIO_RX_R71p,_DIFFOUT_R71p,_DQ9R,_DQ3R)_K21") (pintype "bidirectional"))
    )
    (net (code "148") (name "unconnected-(D4F-IO,_(DIFFIO_RX_R73n,_DIFFOUT_R73n)-PadL21)") (class "Default")
      (node (ref "D4") (pin "L21") (pinfunction "IO,_(DIFFIO_RX_R73n,_DIFFOUT_R73n)_L21") (pintype "bidirectional"))
    )
    (net (code "149") (name "unconnected-(D4F-IO,_(DIFFIO_RX_R73p,_DIFFOUT_R73p)-PadM21)") (class "Default")
      (node (ref "D4") (pin "M21") (pinfunction "IO,_(DIFFIO_RX_R73p,_DIFFOUT_R73p)_M21") (pintype "bidirectional"))
    )
    (net (code "150") (name "unconnected-(D4F-IO,_(DIFFIO_RX_R75n,_DIFFOUT_R75n,_DQ10R,_DQ3R)-PadH26)") (class "Default")
      (node (ref "D4") (pin "H26") (pinfunction "IO,_(DIFFIO_RX_R75n,_DIFFOUT_R75n,_DQ10R,_DQ3R)_H26") (pintype "bidirectional"))
    )
    (net (code "151") (name "unconnected-(D4F-IO,_(DIFFIO_RX_R75p,_DIFFOUT_R75p,_DQ10R,_DQ3R)-PadH25)") (class "Default")
      (node (ref "D4") (pin "H25") (pinfunction "IO,_(DIFFIO_RX_R75p,_DIFFOUT_R75p,_DQ10R,_DQ3R)_H25") (pintype "bidirectional"))
    )
    (net (code "152") (name "unconnected-(D4F-IO,_(DIFFIO_RX_R77n,_DIFFOUT_R77n,_DQSn10R,_DQ3R)-PadN20)") (class "Default")
      (node (ref "D4") (pin "N20") (pinfunction "IO,_(DIFFIO_RX_R77n,_DIFFOUT_R77n,_DQSn10R,_DQ3R)_N20") (pintype "bidirectional"))
    )
    (net (code "153") (name "unconnected-(D4F-IO,_(DIFFIO_RX_R77p,_DIFFOUT_R77p,_DQS10R,_DQ3R)-PadP20)") (class "Default")
      (node (ref "D4") (pin "P20") (pinfunction "IO,_(DIFFIO_RX_R77p,_DIFFOUT_R77p,_DQS10R,_DQ3R)_P20") (pintype "bidirectional"))
    )
    (net (code "154") (name "unconnected-(D4F-IO,_(DIFFIO_RX_R79n,_DIFFOUT_R79n,_DQ10R,_DQ3R)-PadJ23)") (class "Default")
      (node (ref "D4") (pin "J23") (pinfunction "IO,_(DIFFIO_RX_R79n,_DIFFOUT_R79n,_DQ10R,_DQ3R)_J23") (pintype "bidirectional"))
    )
    (net (code "155") (name "unconnected-(D4F-IO,_(DIFFIO_RX_R79p,_DIFFOUT_R79p,_DQ10R,_DQ3R)-PadJ22)") (class "Default")
      (node (ref "D4") (pin "J22") (pinfunction "IO,_(DIFFIO_RX_R79p,_DIFFOUT_R79p,_DQ10R,_DQ3R)_J22") (pintype "bidirectional"))
    )
    (net (code "156") (name "unconnected-(D4F-IO,_(DIFFIO_TX_R62n,_DIFFOUT_R62n,_DQ8R,_DQ2R)-PadG26)") (class "Default")
      (node (ref "D4") (pin "G26") (pinfunction "IO,_(DIFFIO_TX_R62n,_DIFFOUT_R62n,_DQ8R,_DQ2R)_G26") (pintype "bidirectional"))
    )
    (net (code "157") (name "unconnected-(D4F-IO,_(DIFFIO_TX_R62p,_DIFFOUT_R62p)-PadH27)") (class "Default")
      (node (ref "D4") (pin "H27") (pinfunction "IO,_(DIFFIO_TX_R62p,_DIFFOUT_R62p)_H27") (pintype "bidirectional"))
    )
    (net (code "158") (name "unconnected-(D4F-IO,_(DIFFIO_TX_R80p,_DIFFOUT_R80p,_DQ10R,_DQ3R)-PadH24)") (class "Default")
      (node (ref "D4") (pin "H24") (pinfunction "IO,_(DIFFIO_TX_R80p,_DIFFOUT_R80p,_DQ10R,_DQ3R)_H24") (pintype "bidirectional"))
    )
    (net (code "159") (name "unconnected-(D4F-IO,_CLK5n,_(DIFFIO_RX_R41n,_DIFFOUT_R41n)-PadR23)") (class "Default")
      (node (ref "D4") (pin "R23") (pinfunction "IO,_CLK5n,_(DIFFIO_RX_R41n,_DIFFOUT_R41n)_R23") (pintype "bidirectional"))
    )
    (net (code "160") (name "unconnected-(D4F-IO,_CLK5p,_(DIFFIO_RX_R41p,_DIFFOUT_R41p)-PadT23)") (class "Default")
      (node (ref "D4") (pin "T23") (pinfunction "IO,_CLK5p,_(DIFFIO_RX_R41p,_DIFFOUT_R41p)_T23") (pintype "bidirectional"))
    )
  )
)
